# FPGA-IO-BANKS.net
KiCad netlist of a schematic drawn in Altium Designer
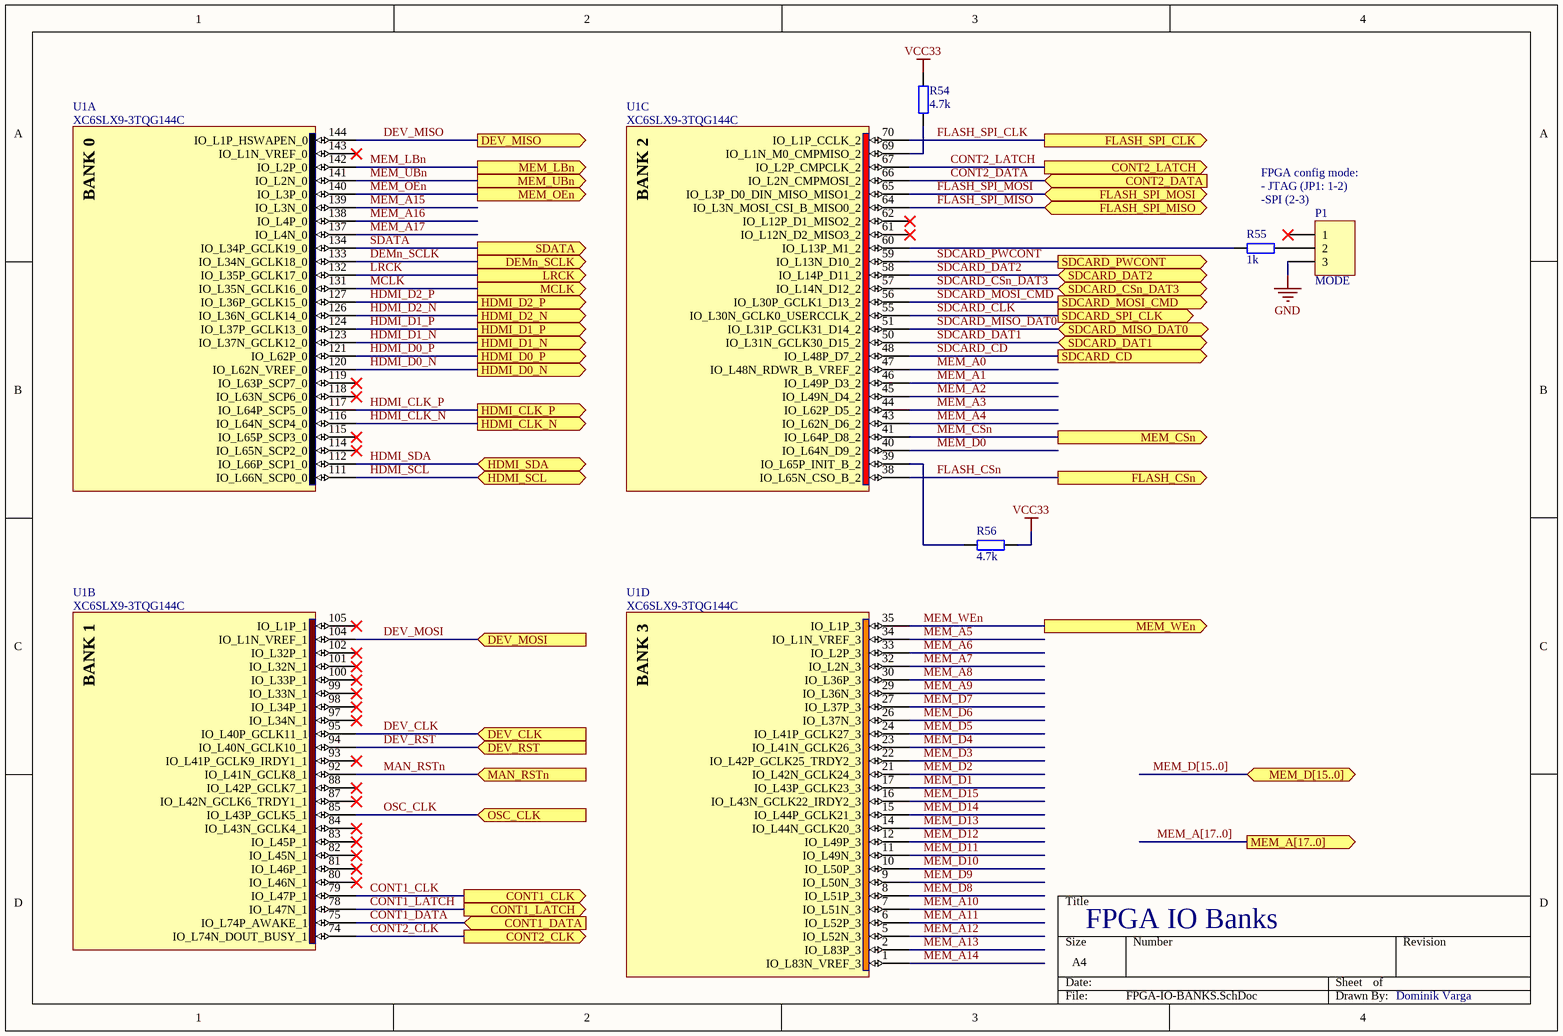
[diagram p0: FPGA-IO-BANKS.SchDoc]

(export (version "E")
  (design (tool "Eeschema 10.0.6"))
  (components
    (comp (ref "P1")
      (value "MODE")
      (footprint "HDR1X3")
      (description "Header, 3-Pin")
      (fields (field (name "PUBLISHER") "Altium Limited"))
      (libsource (lib "Miscellaneous Connectors") (part "Header 3"))
    )
    (comp (ref "R54")
      (value "4.7k")
      (footprint "RES_SMD0603")
      (description "Resistor SMD 0603")
      (libsource (lib "NES-Components") (part "RES_0603"))
    )
    (comp (ref "R55")
      (value "1k")
      (footprint "RES_SMD0603")
      (description "Resistor SMD 0603")
      (libsource (lib "NES-Components") (part "RES_0603"))
    )
    (comp (ref "R56")
      (value "4.7k")
      (footprint "RES_SMD0603")
      (description "Resistor SMD 0603")
      (libsource (lib "NES-Components") (part "RES_0603"))
    )
    (comp (ref "U1")
      (value "XC6SLX9-3TQG144C")
      (footprint "QFP50P2200X2200X160-144N")
      (libsource (lib "NES-Components") (part "XC6SLX9-3TQG144C"))
    )
  )
  (nets
    (net (code "1") (name "/CONT1_CLK") (class "Default")
      (node (ref "U1") (pin "79") (pinfunction "IO_L47P_1_79") (pintype "bidirectional"))
    )
    (net (code "2") (name "/CONT1_DATA") (class "Default")
      (node (ref "U1") (pin "75") (pinfunction "IO_L74P_AWAKE_1_75") (pintype "bidirectional"))
    )
    (net (code "3") (name "/CONT1_LATCH") (class "Default")
      (node (ref "U1") (pin "78") (pinfunction "IO_L47N_1_78") (pintype "bidirectional"))
    )
    (net (code "4") (name "/CONT2_CLK") (class "Default")
      (node (ref "U1") (pin "74") (pinfunction "IO_L74N_DOUT_BUSY_1_74") (pintype "bidirectional"))
    )
    (net (code "5") (name "/CONT2_DATA") (class "Default")
      (node (ref "U1") (pin "66") (pinfunction "IO_L2N_CMPMOSI_2_66") (pintype "bidirectional"))
    )
    (net (code "6") (name "/CONT2_LATCH") (class "Default")
      (node (ref "U1") (pin "67") (pinfunction "IO_L2P_CMPCLK_2_67") (pintype "bidirectional"))
    )
    (net (code "7") (name "/DEMn_SCLK") (class "Default")
      (node (ref "U1") (pin "133") (pinfunction "IO_L34N_GCLK18_0_133") (pintype "bidirectional"))
    )
    (net (code "8") (name "/DEV_CLK") (class "Default")
      (node (ref "U1") (pin "95") (pinfunction "IO_L40P_GCLK11_1_95") (pintype "bidirectional"))
    )
    (net (code "9") (name "/DEV_MISO") (class "Default")
      (node (ref "U1") (pin "144") (pinfunction "IO_L1P_HSWAPEN_0_144") (pintype "bidirectional"))
    )
    (net (code "10") (name "/DEV_MOSI") (class "Default")
      (node (ref "U1") (pin "104") (pinfunction "IO_L1N_VREF_1_104") (pintype "bidirectional"))
    )
    (net (code "11") (name "/DEV_RST") (class "Default")
      (node (ref "U1") (pin "94") (pinfunction "IO_L40N_GCLK10_1_94") (pintype "bidirectional"))
    )
    (net (code "12") (name "/FLASH_CSn") (class "Default")
      (node (ref "U1") (pin "38") (pinfunction "IO_L65N_CSO_B_2_38") (pintype "bidirectional"))
    )
    (net (code "13") (name "/FLASH_SPI_CLK") (class "Default")
      (node (ref "U1") (pin "70") (pinfunction "IO_L1P_CCLK_2_70") (pintype "bidirectional"))
    )
    (net (code "14") (name "/FLASH_SPI_MISO") (class "Default")
      (node (ref "U1") (pin "64") (pinfunction "IO_L3N_MOSI_CSI_B_MISO0_2_64") (pintype "bidirectional"))
    )
    (net (code "15") (name "/FLASH_SPI_MOSI") (class "Default")
      (node (ref "U1") (pin "65") (pinfunction "IO_L3P_D0_DIN_MISO_MISO1_2_65") (pintype "bidirectional"))
    )
    (net (code "16") (name "/HDMI_CLK_N") (class "Default")
      (node (ref "U1") (pin "116") (pinfunction "IO_L64N_SCP4_0_116") (pintype "bidirectional"))
    )
    (net (code "17") (name "/HDMI_CLK_P") (class "Default")
      (node (ref "U1") (pin "117") (pinfunction "IO_L64P_SCP5_0_117") (pintype "bidirectional"))
    )
    (net (code "18") (name "/HDMI_D0_N") (class "Default")
      (node (ref "U1") (pin "120") (pinfunction "IO_L62N_VREF_0_120") (pintype "bidirectional"))
    )
    (net (code "19") (name "/HDMI_D0_P") (class "Default")
      (node (ref "U1") (pin "121") (pinfunction "IO_L62P_0_121") (pintype "bidirectional"))
    )
    (net (code "20") (name "/HDMI_D1_N") (class "Default")
      (node (ref "U1") (pin "123") (pinfunction "IO_L37N_GCLK12_0_123") (pintype "bidirectional"))
    )
    (net (code "21") (name "/HDMI_D1_P") (class "Default")
      (node (ref "U1") (pin "124") (pinfunction "IO_L37P_GCLK13_0_124") (pintype "bidirectional"))
    )
    (net (code "22") (name "/HDMI_D2_N") (class "Default")
      (node (ref "U1") (pin "126") (pinfunction "IO_L36N_GCLK14_0_126") (pintype "bidirectional"))
    )
    (net (code "23") (name "/HDMI_D2_P") (class "Default")
      (node (ref "U1") (pin "127") (pinfunction "IO_L36P_GCLK15_0_127") (pintype "bidirectional"))
    )
    (net (code "24") (name "/HDMI_SCL") (class "Default")
      (node (ref "U1") (pin "111") (pinfunction "IO_L66N_SCP0_0_111") (pintype "bidirectional"))
    )
    (net (code "25") (name "/HDMI_SDA") (class "Default")
      (node (ref "U1") (pin "112") (pinfunction "IO_L66P_SCP1_0_112") (pintype "bidirectional"))
    )
    (net (code "26") (name "/LRCK") (class "Default")
      (node (ref "U1") (pin "132") (pinfunction "IO_L35P_GCLK17_0_132") (pintype "bidirectional"))
    )
    (net (code "27") (name "/MAN_RSTn") (class "Default")
      (node (ref "U1") (pin "92") (pinfunction "IO_L41N_GCLK8_1_92") (pintype "bidirectional"))
    )
    (net (code "28") (name "/MCLK") (class "Default")
      (node (ref "U1") (pin "131") (pinfunction "IO_L35N_GCLK16_0_131") (pintype "bidirectional"))
    )
    (net (code "29") (name "/MEM_A0") (class "Default")
      (node (ref "U1") (pin "47") (pinfunction "IO_L48N_RDWR_B_VREF_2_47") (pintype "bidirectional"))
    )
    (net (code "30") (name "/MEM_A1") (class "Default")
      (node (ref "U1") (pin "46") (pinfunction "IO_L49P_D3_2_46") (pintype "bidirectional"))
    )
    (net (code "31") (name "/MEM_A2") (class "Default")
      (node (ref "U1") (pin "45") (pinfunction "IO_L49N_D4_2_45") (pintype "bidirectional"))
    )
    (net (code "32") (name "/MEM_A3") (class "Default")
      (node (ref "U1") (pin "44") (pinfunction "IO_L62P_D5_2_44") (pintype "bidirectional"))
    )
    (net (code "33") (name "/MEM_A4") (class "Default")
      (node (ref "U1") (pin "43") (pinfunction "IO_L62N_D6_2_43") (pintype "bidirectional"))
    )
    (net (code "34") (name "/MEM_A5") (class "Default")
      (node (ref "U1") (pin "34") (pinfunction "IO_L1N_VREF_3_34") (pintype "bidirectional"))
    )
    (net (code "35") (name "/MEM_A6") (class "Default")
      (node (ref "U1") (pin "33") (pinfunction "IO_L2P_3_33") (pintype "bidirectional"))
    )
    (net (code "36") (name "/MEM_A7") (class "Default")
      (node (ref "U1") (pin "32") (pinfunction "IO_L2N_3_32") (pintype "bidirectional"))
    )
    (net (code "37") (name "/MEM_A8") (class "Default")
      (node (ref "U1") (pin "30") (pinfunction "IO_L36P_3_30") (pintype "bidirectional"))
    )
    (net (code "38") (name "/MEM_A9") (class "Default")
      (node (ref "U1") (pin "29") (pinfunction "IO_L36N_3_29") (pintype "bidirectional"))
    )
    (net (code "39") (name "/MEM_A10") (class "Default")
      (node (ref "U1") (pin "7") (pinfunction "IO_L51N_3_7") (pintype "bidirectional"))
    )
    (net (code "40") (name "/MEM_A11") (class "Default")
      (node (ref "U1") (pin "6") (pinfunction "IO_L52P_3_6") (pintype "bidirectional"))
    )
    (net (code "41") (name "/MEM_A12") (class "Default")
      (node (ref "U1") (pin "5") (pinfunction "IO_L52N_3_5") (pintype "bidirectional"))
    )
    (net (code "42") (name "/MEM_A13") (class "Default")
      (node (ref "U1") (pin "2") (pinfunction "IO_L83P_3_2") (pintype "bidirectional"))
    )
    (net (code "43") (name "/MEM_A14") (class "Default")
      (node (ref "U1") (pin "1") (pinfunction "IO_L83N_VREF_3_1") (pintype "bidirectional"))
    )
    (net (code "44") (name "/MEM_A15") (class "Default")
      (node (ref "U1") (pin "139") (pinfunction "IO_L3N_0_139") (pintype "bidirectional"))
    )
    (net (code "45") (name "/MEM_A16") (class "Default")
      (node (ref "U1") (pin "138") (pinfunction "IO_L4P_0_138") (pintype "bidirectional"))
    )
    (net (code "46") (name "/MEM_A17") (class "Default")
      (node (ref "U1") (pin "137") (pinfunction "IO_L4N_0_137") (pintype "bidirectional"))
    )
    (net (code "48") (name "/MEM_CSn") (class "Default")
      (node (ref "U1") (pin "41") (pinfunction "IO_L64P_D8_2_41") (pintype "bidirectional"))
    )
    (net (code "49") (name "/MEM_D0") (class "Default")
      (node (ref "U1") (pin "40") (pinfunction "IO_L64N_D9_2_40") (pintype "bidirectional"))
    )
    (net (code "50") (name "/MEM_D1") (class "Default")
      (node (ref "U1") (pin "17") (pinfunction "IO_L43P_GCLK23_3_17") (pintype "bidirectional"))
    )
    (net (code "51") (name "/MEM_D2") (class "Default")
      (node (ref "U1") (pin "21") (pinfunction "IO_L42N_GCLK24_3_21") (pintype "bidirectional"))
    )
    (net (code "52") (name "/MEM_D3") (class "Default")
      (node (ref "U1") (pin "22") (pinfunction "IO_L42P_GCLK25_TRDY2_3_22") (pintype "bidirectional"))
    )
    (net (code "53") (name "/MEM_D4") (class "Default")
      (node (ref "U1") (pin "23") (pinfunction "IO_L41N_GCLK26_3_23") (pintype "bidirectional"))
    )
    (net (code "54") (name "/MEM_D5") (class "Default")
      (node (ref "U1") (pin "24") (pinfunction "IO_L41P_GCLK27_3_24") (pintype "bidirectional"))
    )
    (net (code "55") (name "/MEM_D6") (class "Default")
      (node (ref "U1") (pin "26") (pinfunction "IO_L37N_3_26") (pintype "bidirectional"))
    )
    (net (code "56") (name "/MEM_D7") (class "Default")
      (node (ref "U1") (pin "27") (pinfunction "IO_L37P_3_27") (pintype "bidirectional"))
    )
    (net (code "57") (name "/MEM_D8") (class "Default")
      (node (ref "U1") (pin "8") (pinfunction "IO_L51P_3_8") (pintype "bidirectional"))
    )
    (net (code "58") (name "/MEM_D9") (class "Default")
      (node (ref "U1") (pin "9") (pinfunction "IO_L50N_3_9") (pintype "bidirectional"))
    )
    (net (code "59") (name "/MEM_D10") (class "Default")
      (node (ref "U1") (pin "10") (pinfunction "IO_L50P_3_10") (pintype "bidirectional"))
    )
    (net (code "60") (name "/MEM_D11") (class "Default")
      (node (ref "U1") (pin "11") (pinfunction "IO_L49N_3_11") (pintype "bidirectional"))
    )
    (net (code "61") (name "/MEM_D12") (class "Default")
      (node (ref "U1") (pin "12") (pinfunction "IO_L49P_3_12") (pintype "bidirectional"))
    )
    (net (code "62") (name "/MEM_D13") (class "Default")
      (node (ref "U1") (pin "14") (pinfunction "IO_L44N_GCLK20_3_14") (pintype "bidirectional"))
    )
    (net (code "63") (name "/MEM_D14") (class "Default")
      (node (ref "U1") (pin "15") (pinfunction "IO_L44P_GCLK21_3_15") (pintype "bidirectional"))
    )
    (net (code "64") (name "/MEM_D15") (class "Default")
      (node (ref "U1") (pin "16") (pinfunction "IO_L43N_GCLK22_IRDY2_3_16") (pintype "bidirectional"))
    )
    (net (code "66") (name "/MEM_LBn") (class "Default")
      (node (ref "U1") (pin "142") (pinfunction "IO_L2P_0_142") (pintype "bidirectional"))
    )
    (net (code "67") (name "/MEM_OEn") (class "Default")
      (node (ref "U1") (pin "140") (pinfunction "IO_L3P_0_140") (pintype "bidirectional"))
    )
    (net (code "68") (name "/MEM_UBn") (class "Default")
      (node (ref "U1") (pin "141") (pinfunction "IO_L2N_0_141") (pintype "bidirectional"))
    )
    (net (code "69") (name "/MEM_WEn") (class "Default")
      (node (ref "U1") (pin "35") (pinfunction "IO_L1P_3_35") (pintype "bidirectional"))
    )
    (net (code "70") (name "/OSC_CLK") (class "Default")
      (node (ref "U1") (pin "85") (pinfunction "IO_L43P_GCLK5_1_85") (pintype "bidirectional"))
    )
    (net (code "71") (name "/SDATA") (class "Default")
      (node (ref "U1") (pin "134") (pinfunction "IO_L34P_GCLK19_0_134") (pintype "bidirectional"))
    )
    (net (code "72") (name "/SDCARD_CD") (class "Default")
      (node (ref "U1") (pin "48") (pinfunction "IO_L48P_D7_2_48") (pintype "bidirectional"))
    )
    (net (code "73") (name "/SDCARD_CLK") (class "Default")
      (node (ref "U1") (pin "55") (pinfunction "IO_L30N_GCLK0_USERCCLK_2_55") (pintype "bidirectional"))
    )
    (net (code "74") (name "/SDCARD_CSn_DAT3") (class "Default")
      (node (ref "U1") (pin "57") (pinfunction "IO_L14N_D12_2_57") (pintype "bidirectional"))
    )
    (net (code "75") (name "/SDCARD_DAT1") (class "Default")
      (node (ref "U1") (pin "50") (pinfunction "IO_L31N_GCLK30_D15_2_50") (pintype "bidirectional"))
    )
    (net (code "76") (name "/SDCARD_DAT2") (class "Default")
      (node (ref "U1") (pin "58") (pinfunction "IO_L14P_D11_2_58") (pintype "bidirectional"))
    )
    (net (code "77") (name "/SDCARD_MISO_DAT0") (class "Default")
      (node (ref "U1") (pin "51") (pinfunction "IO_L31P_GCLK31_D14_2_51") (pintype "bidirectional"))
    )
    (net (code "78") (name "/SDCARD_MOSI_CMD") (class "Default")
      (node (ref "U1") (pin "56") (pinfunction "IO_L30P_GCLK1_D13_2_56") (pintype "bidirectional"))
    )
    (net (code "79") (name "/SDCARD_PWCONT") (class "Default")
      (node (ref "U1") (pin "59") (pinfunction "IO_L13N_D10_2_59") (pintype "bidirectional"))
    )
    (net (code "80") (name "GND") (class "Default")
      (node (ref "P1") (pin "3") (pinfunction "3_3") (pintype "passive"))
    )
    (net (code "81") (name "Net-(P1-Pad2)") (class "Default")
      (node (ref "P1") (pin "2") (pinfunction "2_2") (pintype "passive"))
      (node (ref "R55") (pin "1") (pinfunction "1_1") (pintype "passive"))
    )
    (net (code "82") (name "Net-(U1C-IO_L1N_M0_CMPMISO_2)") (class "Default")
      (node (ref "R54") (pin "2") (pinfunction "2_2") (pintype "passive"))
      (node (ref "U1") (pin "69") (pinfunction "IO_L1N_M0_CMPMISO_2_69") (pintype "bidirectional"))
    )
    (net (code "83") (name "Net-(U1C-IO_L13P_M1_2)") (class "Default")
      (node (ref "R55") (pin "2") (pinfunction "2_2") (pintype "passive"))
      (node (ref "U1") (pin "60") (pinfunction "IO_L13P_M1_2_60") (pintype "bidirectional"))
    )
    (net (code "84") (name "Net-(U1C-IO_L65P_INIT_B_2)") (class "Default")
      (node (ref "R56") (pin "2") (pinfunction "2_2") (pintype "passive"))
      (node (ref "U1") (pin "39") (pinfunction "IO_L65P_INIT_B_2_39") (pintype "bidirectional"))
    )
    (net (code "85") (name "VCC33") (class "Default")
      (node (ref "R54") (pin "1") (pinfunction "1_1") (pintype "passive"))
      (node (ref "R56") (pin "1") (pinfunction "1_1") (pintype "passive"))
    )
    (net (code "86") (name "unconnected-(P1-Pad1)") (class "Default")
      (node (ref "P1") (pin "1") (pinfunction "1_1") (pintype "passive+no_connect"))
    )
    (net (code "87") (name "unconnected-(U1A-IO_L1N_VREF_0-Pad143)") (class "Default")
      (node (ref "U1") (pin "143") (pinfunction "IO_L1N_VREF_0_143") (pintype "bidirectional+no_connect"))
    )
    (net (code "88") (name "unconnected-(U1A-IO_L63N_SCP6_0-Pad118)") (class "Default")
      (node (ref "U1") (pin "118") (pinfunction "IO_L63N_SCP6_0_118") (pintype "bidirectional+no_connect"))
    )
    (net (code "89") (name "unconnected-(U1A-IO_L63P_SCP7_0-Pad119)") (class "Default")
      (node (ref "U1") (pin "119") (pinfunction "IO_L63P_SCP7_0_119") (pintype "bidirectional+no_connect"))
    )
    (net (code "90") (name "unconnected-(U1A-IO_L65N_SCP2_0-Pad114)") (class "Default")
      (node (ref "U1") (pin "114") (pinfunction "IO_L65N_SCP2_0_114") (pintype "bidirectional+no_connect"))
    )
    (net (code "91") (name "unconnected-(U1A-IO_L65P_SCP3_0-Pad115)") (class "Default")
      (node (ref "U1") (pin "115") (pinfunction "IO_L65P_SCP3_0_115") (pintype "bidirectional+no_connect"))
    )
    (net (code "92") (name "unconnected-(U1B-IO_L1P_1-Pad105)") (class "Default")
      (node (ref "U1") (pin "105") (pinfunction "IO_L1P_1_105") (pintype "bidirectional+no_connect"))
    )
    (net (code "93") (name "unconnected-(U1B-IO_L32N_1-Pad101)") (class "Default")
      (node (ref "U1") (pin "101") (pinfunction "IO_L32N_1_101") (pintype "bidirectional+no_connect"))
    )
    (net (code "94") (name "unconnected-(U1B-IO_L32P_1-Pad102)") (class "Default")
      (node (ref "U1") (pin "102") (pinfunction "IO_L32P_1_102") (pintype "bidirectional+no_connect"))
    )
    (net (code "95") (name "unconnected-(U1B-IO_L33N_1-Pad99)") (class "Default")
      (node (ref "U1") (pin "99") (pinfunction "IO_L33N_1_99") (pintype "bidirectional+no_connect"))
    )
    (net (code "96") (name "unconnected-(U1B-IO_L33P_1-Pad100)") (class "Default")
      (node (ref "U1") (pin "100") (pinfunction "IO_L33P_1_100") (pintype "bidirectional+no_connect"))
    )
    (net (code "97") (name "unconnected-(U1B-IO_L34N_1-Pad97)") (class "Default")
      (node (ref "U1") (pin "97") (pinfunction "IO_L34N_1_97") (pintype "bidirectional+no_connect"))
    )
    (net (code "98") (name "unconnected-(U1B-IO_L34P_1-Pad98)") (class "Default")
      (node (ref "U1") (pin "98") (pinfunction "IO_L34P_1_98") (pintype "bidirectional+no_connect"))
    )
    (net (code "99") (name "unconnected-(U1B-IO_L41P_GCLK9_IRDY1_1-Pad93)") (class "Default")
      (node (ref "U1") (pin "93") (pinfunction "IO_L41P_GCLK9_IRDY1_1_93") (pintype "bidirectional+no_connect"))
    )
    (net (code "100") (name "unconnected-(U1B-IO_L42N_GCLK6_TRDY1_1-Pad87)") (class "Default")
      (node (ref "U1") (pin "87") (pinfunction "IO_L42N_GCLK6_TRDY1_1_87") (pintype "bidirectional+no_connect"))
    )
    (net (code "101") (name "unconnected-(U1B-IO_L42P_GCLK7_1-Pad88)") (class "Default")
      (node (ref "U1") (pin "88") (pinfunction "IO_L42P_GCLK7_1_88") (pintype "bidirectional+no_connect"))
    )
    (net (code "102") (name "unconnected-(U1B-IO_L43N_GCLK4_1-Pad84)") (class "Default")
      (node (ref "U1") (pin "84") (pinfunction "IO_L43N_GCLK4_1_84") (pintype "bidirectional+no_connect"))
    )
    (net (code "103") (name "unconnected-(U1B-IO_L45N_1-Pad82)") (class "Default")
      (node (ref "U1") (pin "82") (pinfunction "IO_L45N_1_82") (pintype "bidirectional+no_connect"))
    )
    (net (code "104") (name "unconnected-(U1B-IO_L45P_1-Pad83)") (class "Default")
      (node (ref "U1") (pin "83") (pinfunction "IO_L45P_1_83") (pintype "bidirectional+no_connect"))
    )
    (net (code "105") (name "unconnected-(U1B-IO_L46N_1-Pad80)") (class "Default")
      (node (ref "U1") (pin "80") (pinfunction "IO_L46N_1_80") (pintype "bidirectional+no_connect"))
    )
    (net (code "106") (name "unconnected-(U1B-IO_L46P_1-Pad81)") (class "Default")
      (node (ref "U1") (pin "81") (pinfunction "IO_L46P_1_81") (pintype "bidirectional+no_connect"))
    )
    (net (code "107") (name "unconnected-(U1C-IO_L12N_D2_MISO3_2-Pad61)") (class "Default")
      (node (ref "U1") (pin "61") (pinfunction "IO_L12N_D2_MISO3_2_61") (pintype "bidirectional+no_connect"))
    )
    (net (code "108") (name "unconnected-(U1C-IO_L12P_D1_MISO2_2-Pad62)") (class "Default")
      (node (ref "U1") (pin "62") (pinfunction "IO_L12P_D1_MISO2_2_62") (pintype "bidirectional+no_connect"))
    )
  )
)
